# enclosure_controller_esp32.net
KiCad netlist of a schematic drawn in EAGLE
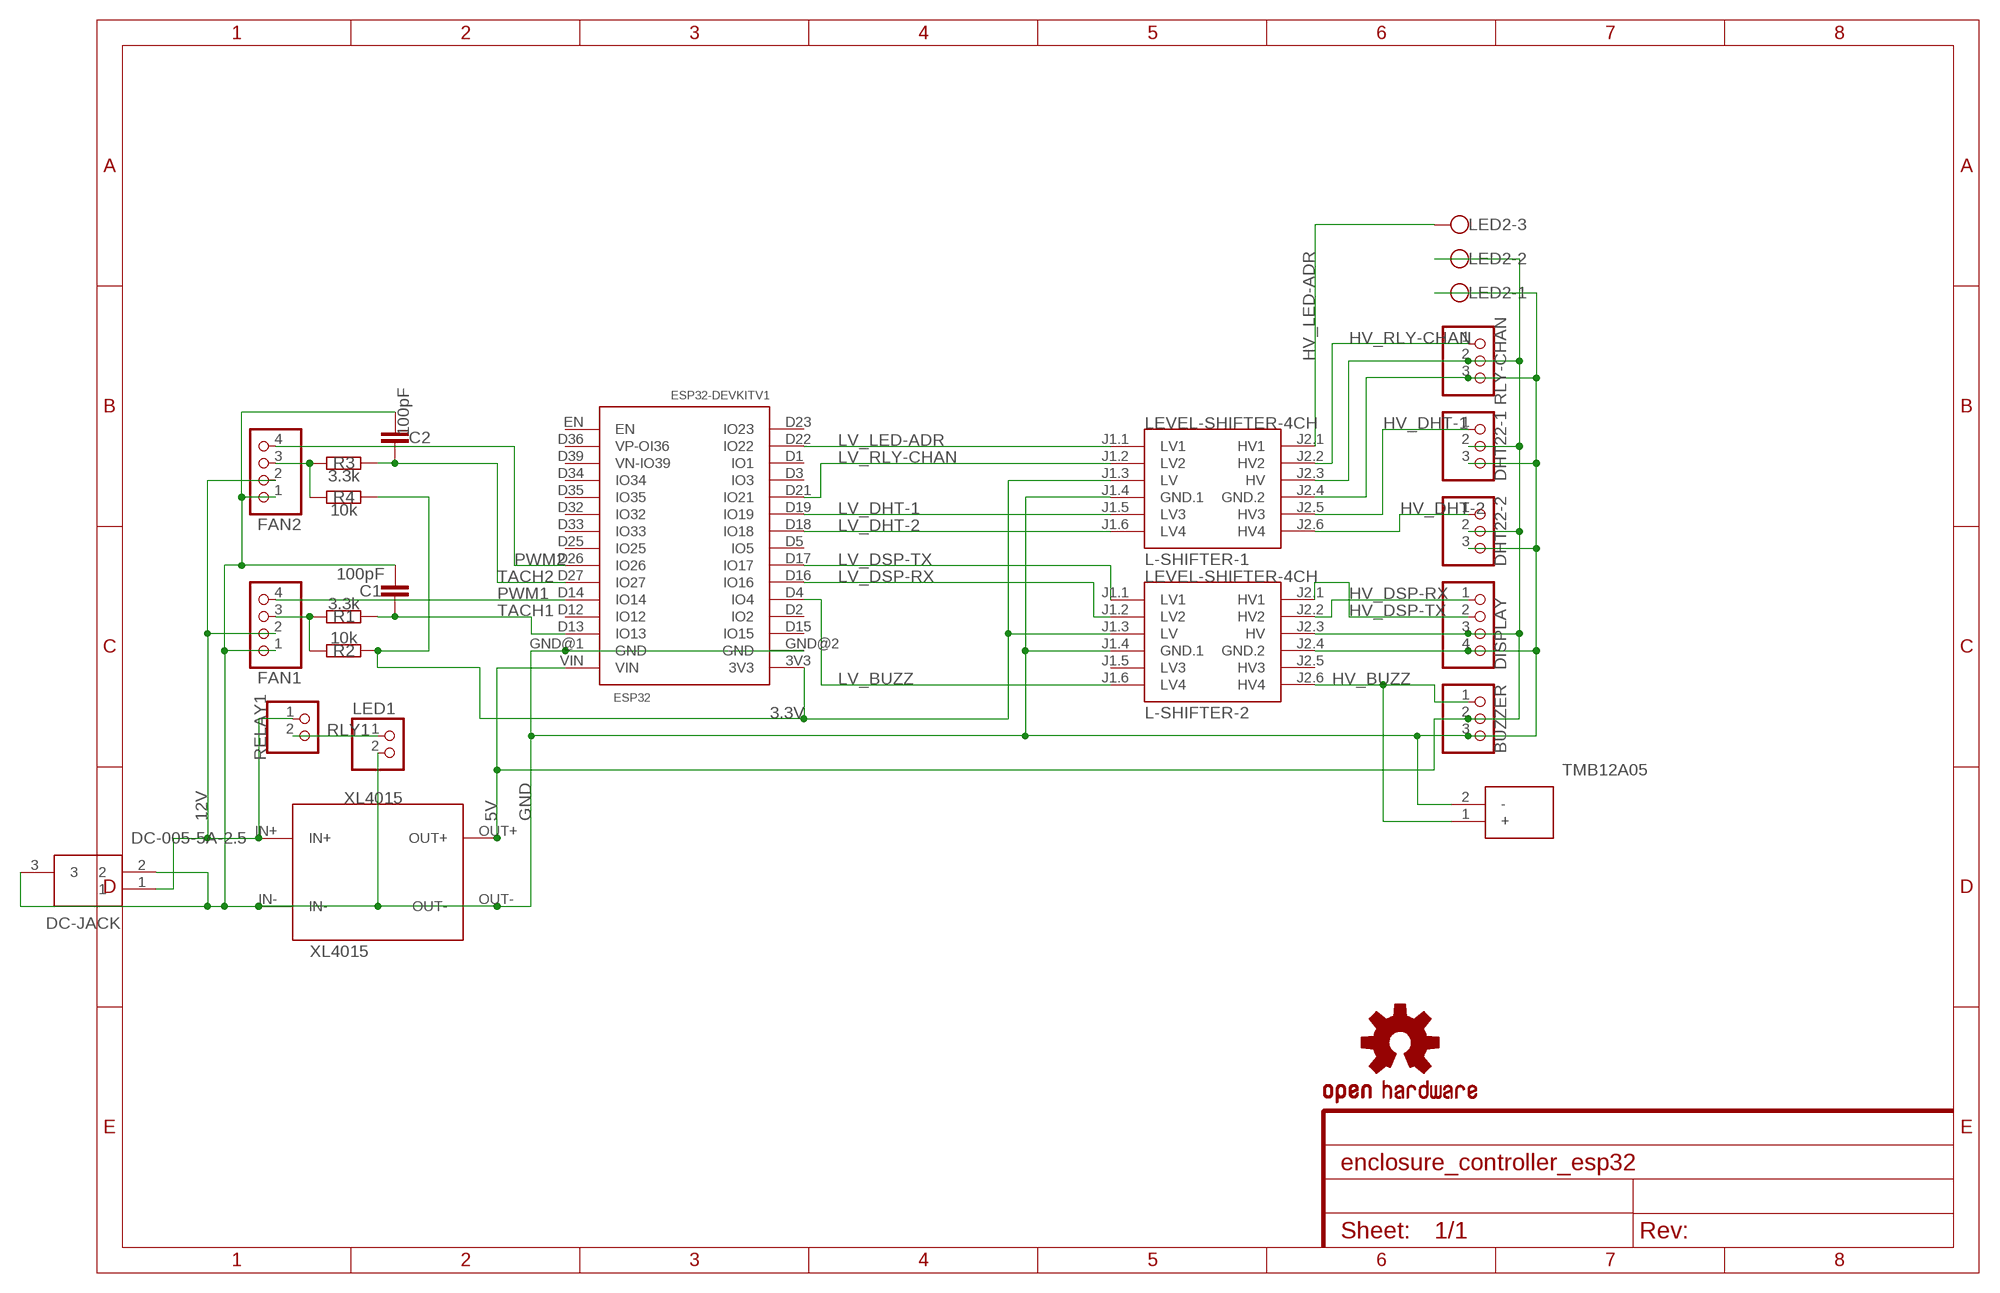
[diagram p0: schematic, sheet 1]

(export (version "E")
  (design (tool "Eeschema 10.0.6"))
  (components
    (comp (ref "BUZZER")
      (value "PINHD-1X3/OCT")
      (footprint "eagle-import:1X03_OCT")
      (libsource (lib "eagle-import") (part "PINHD-1X3/OCT"))
    )
    (comp (ref "C1")
      (value "100pF")
      (footprint "eagle-import:C050-025X075")
      (libsource (lib "eagle-import") (part "C-EU050-025X075"))
    )
    (comp (ref "C2")
      (value "100pF")
      (footprint "eagle-import:C050-025X075")
      (libsource (lib "eagle-import") (part "C-EU050-025X075"))
    )
    (comp (ref "DC-JACK")
      (value "DC-005-5A-2.5")
      (footprint "eagle-import:DC0055A25")
      (libsource (lib "eagle-import") (part "DC-005-5A-2.5"))
    )
    (comp (ref "DHT22-1")
      (value "PINHD-1X3/OCT")
      (footprint "eagle-import:1X03_OCT")
      (libsource (lib "eagle-import") (part "PINHD-1X3/OCT"))
    )
    (comp (ref "DHT22-2")
      (value "PINHD-1X3/OCT")
      (footprint "eagle-import:1X03_OCT")
      (libsource (lib "eagle-import") (part "PINHD-1X3/OCT"))
    )
    (comp (ref "DISPLAY")
      (value "PINHD-1X4/OCT")
      (footprint "eagle-import:1X04_OCT")
      (libsource (lib "eagle-import") (part "PINHD-1X4/OCT"))
    )
    (comp (ref "ESP32")
      (value "ESP32DEVKITV1")
      (footprint "eagle-import:ESP32-DEVKITV1")
      (libsource (lib "eagle-import") (part "ESP32DEVKITV1"))
    )
    (comp (ref "FAN1")
      (value "PINHD-1X4/OCT")
      (footprint "eagle-import:1X04_OCT")
      (libsource (lib "eagle-import") (part "PINHD-1X4/OCT"))
    )
    (comp (ref "FAN2")
      (value "PINHD-1X4/OCT")
      (footprint "eagle-import:1X04_OCT")
      (libsource (lib "eagle-import") (part "PINHD-1X4/OCT"))
    )
    (comp (ref "L-SHIFTER-1")
      (value "LEVEL-SHIFTER-4CH")
      (footprint "eagle-import:LEVEL-SHIFTER-4CH")
      (libsource (lib "eagle-import") (part "LEVEL-SHIFTER-4CH"))
    )
    (comp (ref "L-SHIFTER-2")
      (value "LEVEL-SHIFTER-4CH")
      (footprint "eagle-import:LEVEL-SHIFTER-4CH")
      (libsource (lib "eagle-import") (part "LEVEL-SHIFTER-4CH"))
    )
    (comp (ref "LED1")
      (value "PINHD-1X2/OCT")
      (footprint "eagle-import:1X02_OCT")
      (libsource (lib "eagle-import") (part "PINHD-1X2/OCT"))
    )
    (comp (ref "LED2")
      (value "LED2-ADR")
      (footprint "eagle-import:W237-103")
      (fields (field (name "MPN") "237-103"))
      (libsource (lib "eagle-import") (part "W237-103"))
    )
    (comp (ref "LOGO1")
      (value "OSHW-LOGOM")
      (footprint "eagle-import:OSHW-LOGO-M")
      (libsource (lib "eagle-import") (part "OSHW-LOGOM"))
    )
    (comp (ref "LS1")
      (value "TMB12A05")
      (footprint "eagle-import:TMB12A05")
      (libsource (lib "eagle-import") (part "TMB12A05"))
    )
    (comp (ref "R1")
      (value "3.3k")
      (footprint "eagle-import:0207_10")
      (libsource (lib "eagle-import") (part "R-EU_0207/10"))
    )
    (comp (ref "R2")
      (value "10k")
      (footprint "eagle-import:0207_10")
      (libsource (lib "eagle-import") (part "R-EU_0207/10"))
    )
    (comp (ref "R3")
      (value "3.3k")
      (footprint "eagle-import:0207_10")
      (libsource (lib "eagle-import") (part "R-EU_0207/10"))
    )
    (comp (ref "R4")
      (value "10k")
      (footprint "eagle-import:0207_10")
      (libsource (lib "eagle-import") (part "R-EU_0207/10"))
    )
    (comp (ref "RELAY1")
      (value "PINHD-1X2/OCT")
      (footprint "eagle-import:1X02_OCT")
      (libsource (lib "eagle-import") (part "PINHD-1X2/OCT"))
    )
    (comp (ref "RLY-CHAN")
      (value "PINHD-1X3/OCT")
      (footprint "eagle-import:1X03_OCT")
      (libsource (lib "eagle-import") (part "PINHD-1X3/OCT"))
    )
    (comp (ref "XL4015")
      (value "XL4015")
      (footprint "eagle-import:XL4015")
      (libsource (lib "eagle-import") (part "XL4015"))
    )
  )
  (nets
    (net (code "1") (name "/3.3V") (class "Default")
      (node (ref "ESP32") (pin "3V3") (pinfunction "3V3_3V3") (pintype "bidirectional"))
      (node (ref "L-SHIFTER-1") (pin "J1.3") (pinfunction "LV_J1.3") (pintype "power_in"))
      (node (ref "L-SHIFTER-2") (pin "J1.3") (pinfunction "LV_J1.3") (pintype "power_in"))
      (node (ref "R2") (pin "1") (pinfunction "1_1") (pintype "passive"))
      (node (ref "R4") (pin "1") (pinfunction "1_1") (pintype "passive"))
    )
    (net (code "2") (name "/5V") (class "Default")
      (node (ref "BUZZER") (pin "2") (pinfunction "2_2") (pintype "passive"))
      (node (ref "DHT22-1") (pin "2") (pinfunction "2_2") (pintype "passive"))
      (node (ref "DHT22-2") (pin "2") (pinfunction "2_2") (pintype "passive"))
      (node (ref "DISPLAY") (pin "3") (pinfunction "3_3") (pintype "passive"))
      (node (ref "ESP32") (pin "VIN") (pinfunction "VIN_VIN") (pintype "bidirectional"))
      (node (ref "L-SHIFTER-1") (pin "J2.3") (pinfunction "HV_J2.3") (pintype "power_in"))
      (node (ref "L-SHIFTER-2") (pin "J2.3") (pinfunction "HV_J2.3") (pintype "power_in"))
      (node (ref "LED2") (pin "2") (pinfunction "KL_2") (pintype "passive"))
      (node (ref "RLY-CHAN") (pin "2") (pinfunction "2_2") (pintype "passive"))
      (node (ref "XL4015") (pin "OUT+") (pinfunction "OUT+_OUT+") (pintype "bidirectional"))
    )
    (net (code "3") (name "/12V") (class "Default")
      (node (ref "DC-JACK") (pin "1") (pinfunction "1_1") (pintype "bidirectional"))
      (node (ref "FAN1") (pin "2") (pinfunction "2_2") (pintype "passive"))
      (node (ref "FAN2") (pin "2") (pinfunction "2_2") (pintype "passive"))
      (node (ref "RELAY1") (pin "1") (pinfunction "1_1") (pintype "passive"))
      (node (ref "XL4015") (pin "IN+") (pinfunction "IN+_IN+") (pintype "bidirectional"))
    )
    (net (code "4") (name "/GND") (class "Default")
      (node (ref "BUZZER") (pin "3") (pinfunction "3_3") (pintype "passive"))
      (node (ref "C1") (pin "2") (pinfunction "2_2") (pintype "passive"))
      (node (ref "C2") (pin "1") (pinfunction "1_1") (pintype "passive"))
      (node (ref "DC-JACK") (pin "2") (pinfunction "2_2") (pintype "bidirectional"))
      (node (ref "DC-JACK") (pin "3") (pinfunction "3_3") (pintype "bidirectional"))
      (node (ref "DHT22-1") (pin "3") (pinfunction "3_3") (pintype "passive"))
      (node (ref "DHT22-2") (pin "3") (pinfunction "3_3") (pintype "passive"))
      (node (ref "DISPLAY") (pin "4") (pinfunction "4_4") (pintype "passive"))
      (node (ref "ESP32") (pin "GND@1") (pinfunction "GND_GND@1") (pintype "bidirectional"))
      (node (ref "ESP32") (pin "GND@2") (pinfunction "GND_GND@2") (pintype "bidirectional"))
      (node (ref "FAN1") (pin "1") (pinfunction "1_1") (pintype "passive"))
      (node (ref "FAN2") (pin "1") (pinfunction "1_1") (pintype "passive"))
      (node (ref "L-SHIFTER-1") (pin "J1.4") (pinfunction "GND.1_J1.4") (pintype "power_in"))
      (node (ref "L-SHIFTER-1") (pin "J2.4") (pinfunction "GND.2_J2.4") (pintype "power_in"))
      (node (ref "L-SHIFTER-2") (pin "J1.4") (pinfunction "GND.1_J1.4") (pintype "power_in"))
      (node (ref "L-SHIFTER-2") (pin "J2.4") (pinfunction "GND.2_J2.4") (pintype "power_in"))
      (node (ref "LED1") (pin "2") (pinfunction "2_2") (pintype "passive"))
      (node (ref "LED2") (pin "1") (pinfunction "KL_1") (pintype "passive"))
      (node (ref "LS1") (pin "2") (pinfunction "-_2") (pintype "bidirectional"))
      (node (ref "RLY-CHAN") (pin "3") (pinfunction "3_3") (pintype "passive"))
      (node (ref "XL4015") (pin "IN-") (pinfunction "IN-_IN-") (pintype "bidirectional"))
      (node (ref "XL4015") (pin "OUT-") (pinfunction "OUT-_OUT-") (pintype "bidirectional"))
    )
    (net (code "5") (name "/HV_BUZZ") (class "Default")
      (node (ref "BUZZER") (pin "1") (pinfunction "1_1") (pintype "passive"))
      (node (ref "L-SHIFTER-2") (pin "J2.6") (pinfunction "HV4_J2.6") (pintype "bidirectional"))
      (node (ref "LS1") (pin "1") (pinfunction "+_1") (pintype "bidirectional"))
    )
    (net (code "6") (name "/HV_DHT-1") (class "Default")
      (node (ref "DHT22-1") (pin "1") (pinfunction "1_1") (pintype "passive"))
      (node (ref "L-SHIFTER-1") (pin "J2.5") (pinfunction "HV3_J2.5") (pintype "bidirectional"))
    )
    (net (code "7") (name "/HV_DHT-2") (class "Default")
      (node (ref "DHT22-2") (pin "1") (pinfunction "1_1") (pintype "passive"))
      (node (ref "L-SHIFTER-1") (pin "J2.6") (pinfunction "HV4_J2.6") (pintype "bidirectional"))
    )
    (net (code "8") (name "/HV_DSP-RX") (class "Default")
      (node (ref "DISPLAY") (pin "1") (pinfunction "1_1") (pintype "passive"))
      (node (ref "L-SHIFTER-2") (pin "J2.2") (pinfunction "HV2_J2.2") (pintype "bidirectional"))
    )
    (net (code "9") (name "/HV_DSP-TX") (class "Default")
      (node (ref "DISPLAY") (pin "2") (pinfunction "2_2") (pintype "passive"))
      (node (ref "L-SHIFTER-2") (pin "J2.1") (pinfunction "HV1_J2.1") (pintype "bidirectional"))
    )
    (net (code "10") (name "/HV_LED-ADR") (class "Default")
      (node (ref "L-SHIFTER-1") (pin "J2.1") (pinfunction "HV1_J2.1") (pintype "bidirectional"))
      (node (ref "LED2") (pin "3") (pinfunction "KL_3") (pintype "passive"))
    )
    (net (code "11") (name "/HV_RLY-CHAN") (class "Default")
      (node (ref "L-SHIFTER-1") (pin "J2.2") (pinfunction "HV2_J2.2") (pintype "bidirectional"))
      (node (ref "RLY-CHAN") (pin "1") (pinfunction "1_1") (pintype "passive"))
    )
    (net (code "12") (name "/LV_BUZZ") (class "Default")
      (node (ref "ESP32") (pin "D4") (pinfunction "IO4_D4") (pintype "bidirectional"))
      (node (ref "L-SHIFTER-2") (pin "J1.6") (pinfunction "LV4_J1.6") (pintype "bidirectional"))
    )
    (net (code "13") (name "/LV_DHT-1") (class "Default")
      (node (ref "ESP32") (pin "D19") (pinfunction "IO19_D19") (pintype "bidirectional"))
      (node (ref "L-SHIFTER-1") (pin "J1.5") (pinfunction "LV3_J1.5") (pintype "bidirectional"))
    )
    (net (code "14") (name "/LV_DHT-2") (class "Default")
      (node (ref "ESP32") (pin "D18") (pinfunction "IO18_D18") (pintype "bidirectional"))
      (node (ref "L-SHIFTER-1") (pin "J1.6") (pinfunction "LV4_J1.6") (pintype "bidirectional"))
    )
    (net (code "15") (name "/LV_DSP-RX") (class "Default")
      (node (ref "ESP32") (pin "D16") (pinfunction "IO16_D16") (pintype "bidirectional"))
      (node (ref "L-SHIFTER-2") (pin "J1.2") (pinfunction "LV2_J1.2") (pintype "bidirectional"))
    )
    (net (code "16") (name "/LV_DSP-TX") (class "Default")
      (node (ref "ESP32") (pin "D17") (pinfunction "IO17_D17") (pintype "bidirectional"))
      (node (ref "L-SHIFTER-2") (pin "J1.1") (pinfunction "LV1_J1.1") (pintype "bidirectional"))
    )
    (net (code "17") (name "/LV_LED-ADR") (class "Default")
      (node (ref "ESP32") (pin "D22") (pinfunction "IO22_D22") (pintype "bidirectional"))
      (node (ref "L-SHIFTER-1") (pin "J1.1") (pinfunction "LV1_J1.1") (pintype "bidirectional"))
    )
    (net (code "18") (name "/LV_RLY-CHAN") (class "Default")
      (node (ref "ESP32") (pin "D21") (pinfunction "IO21_D21") (pintype "bidirectional"))
      (node (ref "L-SHIFTER-1") (pin "J1.2") (pinfunction "LV2_J1.2") (pintype "bidirectional"))
    )
    (net (code "19") (name "/PWM1") (class "Default")
      (node (ref "ESP32") (pin "D14") (pinfunction "IO14_D14") (pintype "bidirectional"))
      (node (ref "FAN1") (pin "4") (pinfunction "4_4") (pintype "passive"))
    )
    (net (code "20") (name "/PWM2") (class "Default")
      (node (ref "ESP32") (pin "D26") (pinfunction "IO26_D26") (pintype "bidirectional"))
      (node (ref "FAN2") (pin "4") (pinfunction "4_4") (pintype "passive"))
    )
    (net (code "21") (name "/RLY1") (class "Default")
      (node (ref "LED1") (pin "1") (pinfunction "1_1") (pintype "passive"))
      (node (ref "RELAY1") (pin "2") (pinfunction "2_2") (pintype "passive"))
    )
    (net (code "22") (name "/TACH1") (class "Default")
      (node (ref "C1") (pin "1") (pinfunction "1_1") (pintype "passive"))
      (node (ref "ESP32") (pin "D13") (pinfunction "IO13_D13") (pintype "bidirectional"))
      (node (ref "FAN1") (pin "3") (pinfunction "3_3") (pintype "passive"))
      (node (ref "R1") (pin "1") (pinfunction "1_1") (pintype "passive"))
      (node (ref "R1") (pin "2") (pinfunction "2_2") (pintype "passive"))
      (node (ref "R2") (pin "2") (pinfunction "2_2") (pintype "passive"))
    )
    (net (code "23") (name "/TACH2") (class "Default")
      (node (ref "C2") (pin "2") (pinfunction "2_2") (pintype "passive"))
      (node (ref "ESP32") (pin "D27") (pinfunction "IO27_D27") (pintype "bidirectional"))
      (node (ref "FAN2") (pin "3") (pinfunction "3_3") (pintype "passive"))
      (node (ref "R3") (pin "1") (pinfunction "1_1") (pintype "passive"))
      (node (ref "R3") (pin "2") (pinfunction "2_2") (pintype "passive"))
      (node (ref "R4") (pin "2") (pinfunction "2_2") (pintype "passive"))
    )
    (net (code "24") (name "unconnected-(ESP32-IO1-PadD1)") (class "Default")
      (node (ref "ESP32") (pin "D1") (pinfunction "IO1_D1") (pintype "bidirectional"))
    )
    (net (code "25") (name "unconnected-(ESP32-IO2-PadD2)") (class "Default")
      (node (ref "ESP32") (pin "D2") (pinfunction "IO2_D2") (pintype "bidirectional"))
    )
    (net (code "26") (name "unconnected-(ESP32-IO3-PadD3)") (class "Default")
      (node (ref "ESP32") (pin "D3") (pinfunction "IO3_D3") (pintype "bidirectional"))
    )
    (net (code "27") (name "unconnected-(ESP32-IO5-PadD5)") (class "Default")
      (node (ref "ESP32") (pin "D5") (pinfunction "IO5_D5") (pintype "bidirectional"))
    )
    (net (code "28") (name "unconnected-(ESP32-IO12-PadD12)") (class "Default")
      (node (ref "ESP32") (pin "D12") (pinfunction "IO12_D12") (pintype "bidirectional"))
    )
    (net (code "29") (name "unconnected-(ESP32-IO15-PadD15)") (class "Default")
      (node (ref "ESP32") (pin "D15") (pinfunction "IO15_D15") (pintype "bidirectional"))
    )
    (net (code "30") (name "unconnected-(ESP32-IO23-PadD23)") (class "Default")
      (node (ref "ESP32") (pin "D23") (pinfunction "IO23_D23") (pintype "bidirectional"))
    )
    (net (code "31") (name "unconnected-(ESP32-IO25-PadD25)") (class "Default")
      (node (ref "ESP32") (pin "D25") (pinfunction "IO25_D25") (pintype "bidirectional"))
    )
    (net (code "32") (name "unconnected-(ESP32-IO32-PadD32)") (class "Default")
      (node (ref "ESP32") (pin "D32") (pinfunction "IO32_D32") (pintype "bidirectional"))
    )
    (net (code "33") (name "unconnected-(ESP32-IO33-PadD33)") (class "Default")
      (node (ref "ESP32") (pin "D33") (pinfunction "IO33_D33") (pintype "bidirectional"))
    )
    (net (code "34") (name "unconnected-(ESP32-IO34-PadD34)") (class "Default")
      (node (ref "ESP32") (pin "D34") (pinfunction "IO34_D34") (pintype "bidirectional"))
    )
    (net (code "35") (name "unconnected-(ESP32-IO35-PadD35)") (class "Default")
      (node (ref "ESP32") (pin "D35") (pinfunction "IO35_D35") (pintype "bidirectional"))
    )
    (net (code "36") (name "unconnected-(ESP32-PadEN)") (class "Default")
      (node (ref "ESP32") (pin "EN") (pinfunction "EN_EN") (pintype "bidirectional"))
    )
    (net (code "37") (name "unconnected-(ESP32-VN-IO39-PadD39)") (class "Default")
      (node (ref "ESP32") (pin "D39") (pinfunction "VN-IO39_D39") (pintype "bidirectional"))
    )
    (net (code "38") (name "unconnected-(ESP32-VP-OI36-PadD36)") (class "Default")
      (node (ref "ESP32") (pin "D36") (pinfunction "VP-OI36_D36") (pintype "bidirectional"))
    )
    (net (code "39") (name "unconnected-(L-SHIFTER-2-HV3-PadJ2.5)") (class "Default")
      (node (ref "L-SHIFTER-2") (pin "J2.5") (pinfunction "HV3_J2.5") (pintype "bidirectional"))
    )
    (net (code "40") (name "unconnected-(L-SHIFTER-2-LV3-PadJ1.5)") (class "Default")
      (node (ref "L-SHIFTER-2") (pin "J1.5") (pinfunction "LV3_J1.5") (pintype "bidirectional"))
    )
  )
)
